# PCF8563-Bob-v1_0.net
KiCad netlist of a schematic drawn in EAGLE
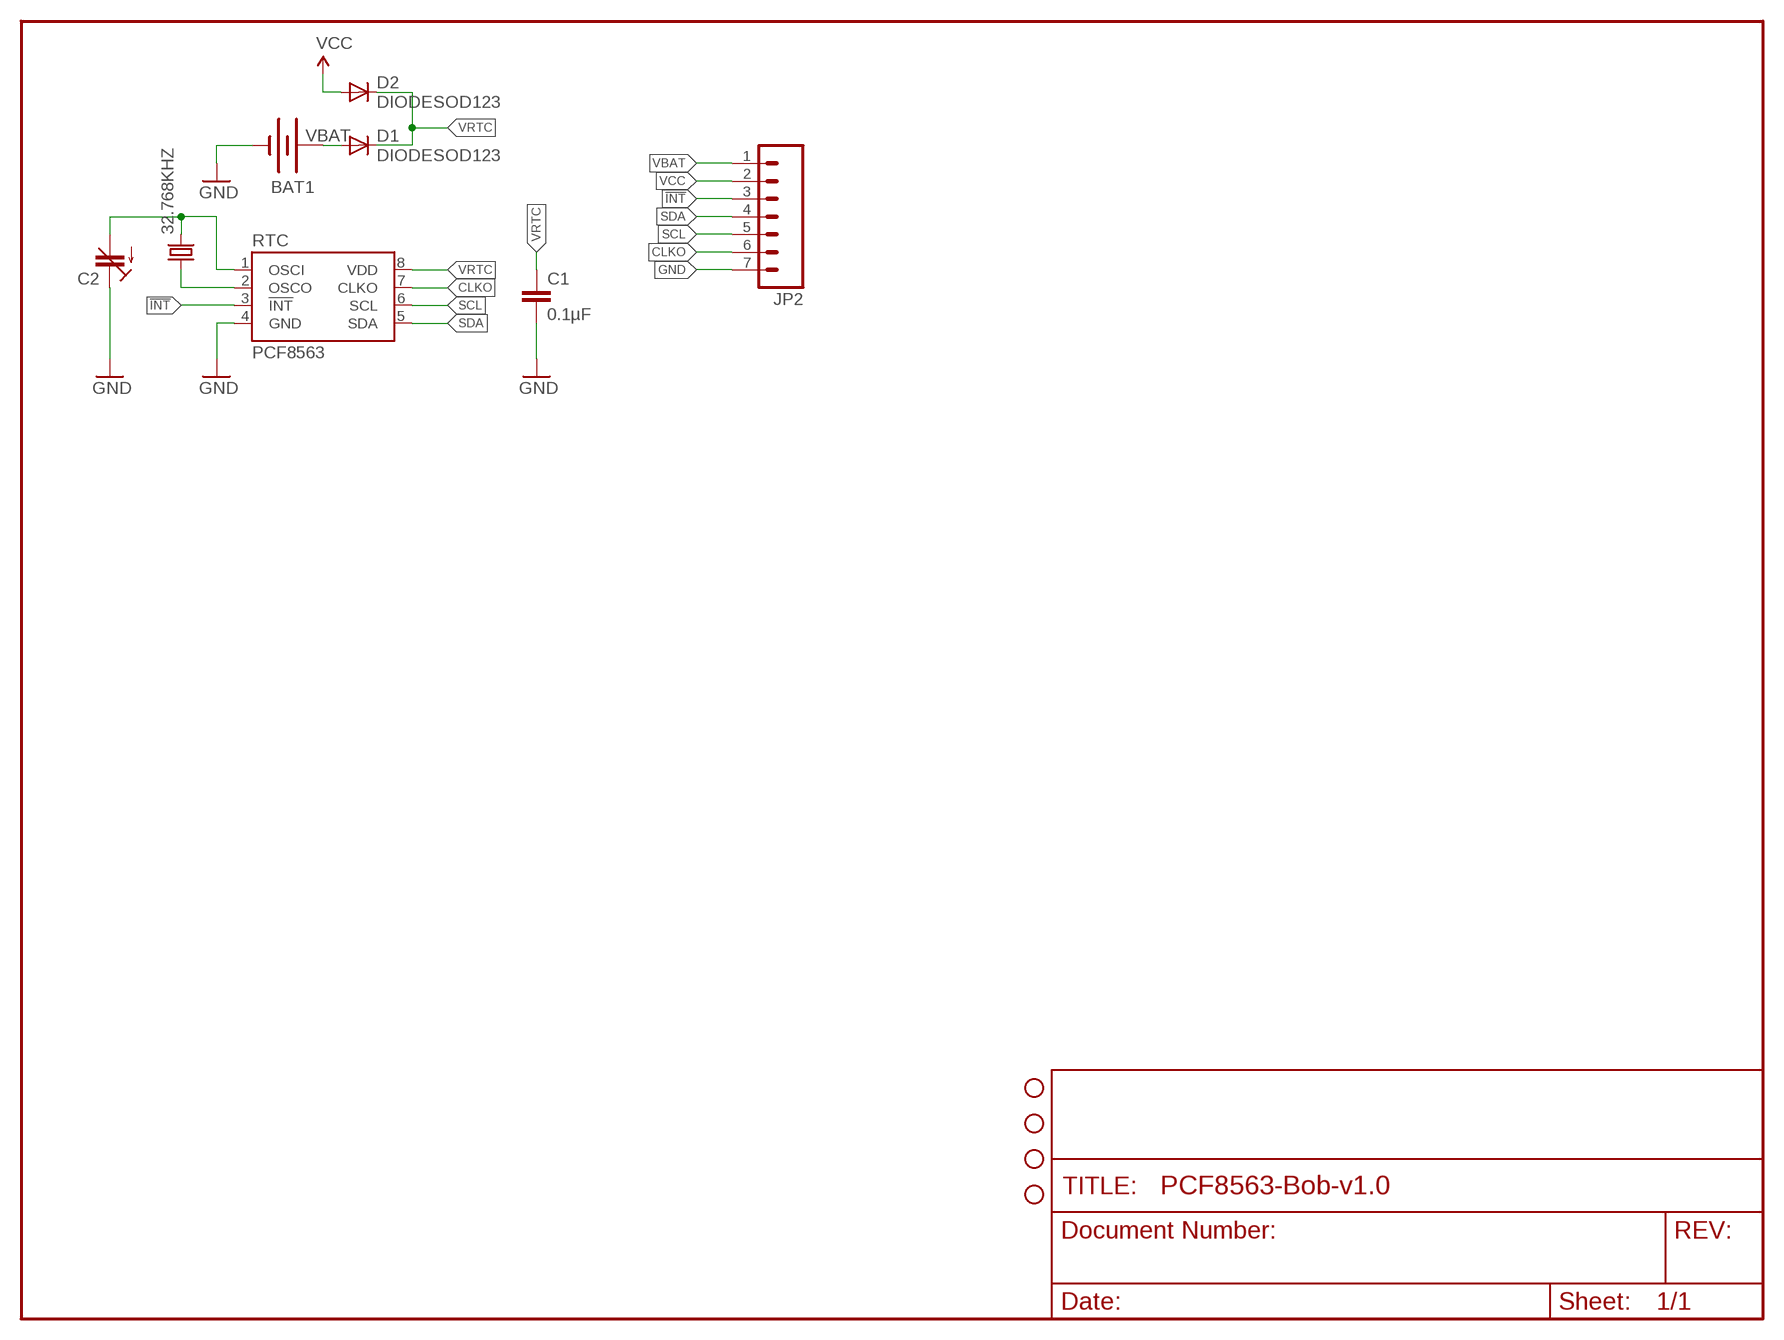
[diagram p0: schematic, sheet 1]

(export (version "E")
  (design (tool "Eeschema 10.0.6"))
  (components
    (comp (ref "32.768KHZ")
      (value "CRYSTAL32-SMD")
      (footprint "eagle-import:CRYSTAL-32KHZ-SMD")
      (libsource (lib "eagle-import") (part "CRYSTAL32-SMD"))
    )
    (comp (ref "BAT1")
      (value "BATTERY12SMD")
      (footprint "eagle-import:HOLDER12SMD")
      (libsource (lib "eagle-import") (part "BATTERY12SMD"))
    )
    (comp (ref "C1")
      (value "0.1µF")
      (footprint "eagle-import:1206")
      (libsource (lib "eagle-import") (part "CAP1206"))
    )
    (comp (ref "C2")
      (value "C-TRIMMTZC3")
      (footprint "eagle-import:CTRIMTZC3")
      (libsource (lib "eagle-import") (part "C-TRIMMTZC3"))
    )
    (comp (ref "D1")
      (value "DIODESOD123")
      (footprint "eagle-import:SOD123")
      (libsource (lib "eagle-import") (part "DIODESOD123"))
    )
    (comp (ref "D2")
      (value "DIODESOD123")
      (footprint "eagle-import:SOD123")
      (libsource (lib "eagle-import") (part "DIODESOD123"))
    )
    (comp (ref "JP2")
      (value "M07")
      (footprint "eagle-import:1X07")
      (libsource (lib "eagle-import") (part "M07"))
    )
    (comp (ref "RTC")
      (value "PCF8563")
      (footprint "eagle-import:DIL-08")
      (libsource (lib "eagle-import") (part "RTCPCF8563"))
    )
    (comp (ref "STANDOFF1")
      (value "STAND-OFF")
      (footprint "eagle-import:STAND-OFF")
      (libsource (lib "eagle-import") (part "STAND-OFF"))
    )
    (comp (ref "STANDOFF2")
      (value "STAND-OFF")
      (footprint "eagle-import:STAND-OFF")
      (libsource (lib "eagle-import") (part "STAND-OFF"))
    )
    (comp (ref "STANDOFF3")
      (value "STAND-OFF")
      (footprint "eagle-import:STAND-OFF")
      (libsource (lib "eagle-import") (part "STAND-OFF"))
    )
    (comp (ref "STANDOFF4")
      (value "STAND-OFF")
      (footprint "eagle-import:STAND-OFF")
      (libsource (lib "eagle-import") (part "STAND-OFF"))
    )
  )
  (nets
    (net (code "1") (name "/~{INT}") (class "Default")
      (node (ref "JP2") (pin "3") (pinfunction "3_3") (pintype "passive"))
      (node (ref "RTC") (pin "3") (pinfunction "~{INT}_3") (pintype "output"))
    )
    (net (code "2") (name "CLKO") (class "Default")
      (node (ref "JP2") (pin "6") (pinfunction "6_6") (pintype "passive"))
      (node (ref "RTC") (pin "7") (pinfunction "CLKO_7") (pintype "output"))
    )
    (net (code "3") (name "GND") (class "Default")
      (node (ref "BAT1") (pin "GND") (pinfunction "-_GND") (pintype "power_in"))
      (node (ref "C1") (pin "2") (pinfunction "2_2") (pintype "passive"))
      (node (ref "C2") (pin "2") (pinfunction "E_2") (pintype "passive"))
      (node (ref "JP2") (pin "7") (pinfunction "7_7") (pintype "passive"))
      (node (ref "RTC") (pin "4") (pinfunction "GND_4") (pintype "power_in"))
    )
    (net (code "4") (name "Net-(32.768KHZ-1)") (class "Default")
      (node (ref "32.768KHZ") (pin "X1") (pinfunction "1_X1") (pintype "passive"))
      (node (ref "RTC") (pin "2") (pinfunction "OSCO_2") (pintype "bidirectional"))
    )
    (net (code "5") (name "Net-(32.768KHZ-2)") (class "Default")
      (node (ref "32.768KHZ") (pin "X2") (pinfunction "2_X2") (pintype "passive"))
      (node (ref "C2") (pin "1") (pinfunction "A_1") (pintype "passive"))
      (node (ref "RTC") (pin "1") (pinfunction "OSCI_1") (pintype "bidirectional"))
    )
    (net (code "6") (name "SCL") (class "Default")
      (node (ref "JP2") (pin "5") (pinfunction "5_5") (pintype "passive"))
      (node (ref "RTC") (pin "6") (pinfunction "SCL_6") (pintype "bidirectional"))
    )
    (net (code "7") (name "SDA") (class "Default")
      (node (ref "JP2") (pin "4") (pinfunction "4_4") (pintype "passive"))
      (node (ref "RTC") (pin "5") (pinfunction "SDA_5") (pintype "bidirectional"))
    )
    (net (code "8") (name "VBAT") (class "Default")
      (node (ref "BAT1") (pin "PWR@1") (pinfunction "+_PWR@1") (pintype "power_in"))
      (node (ref "BAT1") (pin "PWR@2") (pinfunction "+_PWR@2") (pintype "power_in"))
      (node (ref "D1") (pin "1-A") (pinfunction "A_1-A") (pintype "passive"))
      (node (ref "JP2") (pin "1") (pinfunction "1_1") (pintype "passive"))
    )
    (net (code "9") (name "VCC") (class "Default")
      (node (ref "D2") (pin "1-A") (pinfunction "A_1-A") (pintype "passive"))
      (node (ref "JP2") (pin "2") (pinfunction "2_2") (pintype "passive"))
    )
    (net (code "10") (name "VRTC") (class "Default")
      (node (ref "C1") (pin "1") (pinfunction "1_1") (pintype "passive"))
      (node (ref "D1") (pin "2-C") (pinfunction "C_2-C") (pintype "passive"))
      (node (ref "D2") (pin "2-C") (pinfunction "C_2-C") (pintype "passive"))
      (node (ref "RTC") (pin "8") (pinfunction "VDD_8") (pintype "bidirectional"))
    )
  )
)
